# barrieren-a-2.net
KiCad netlist of a schematic drawn in EAGLE
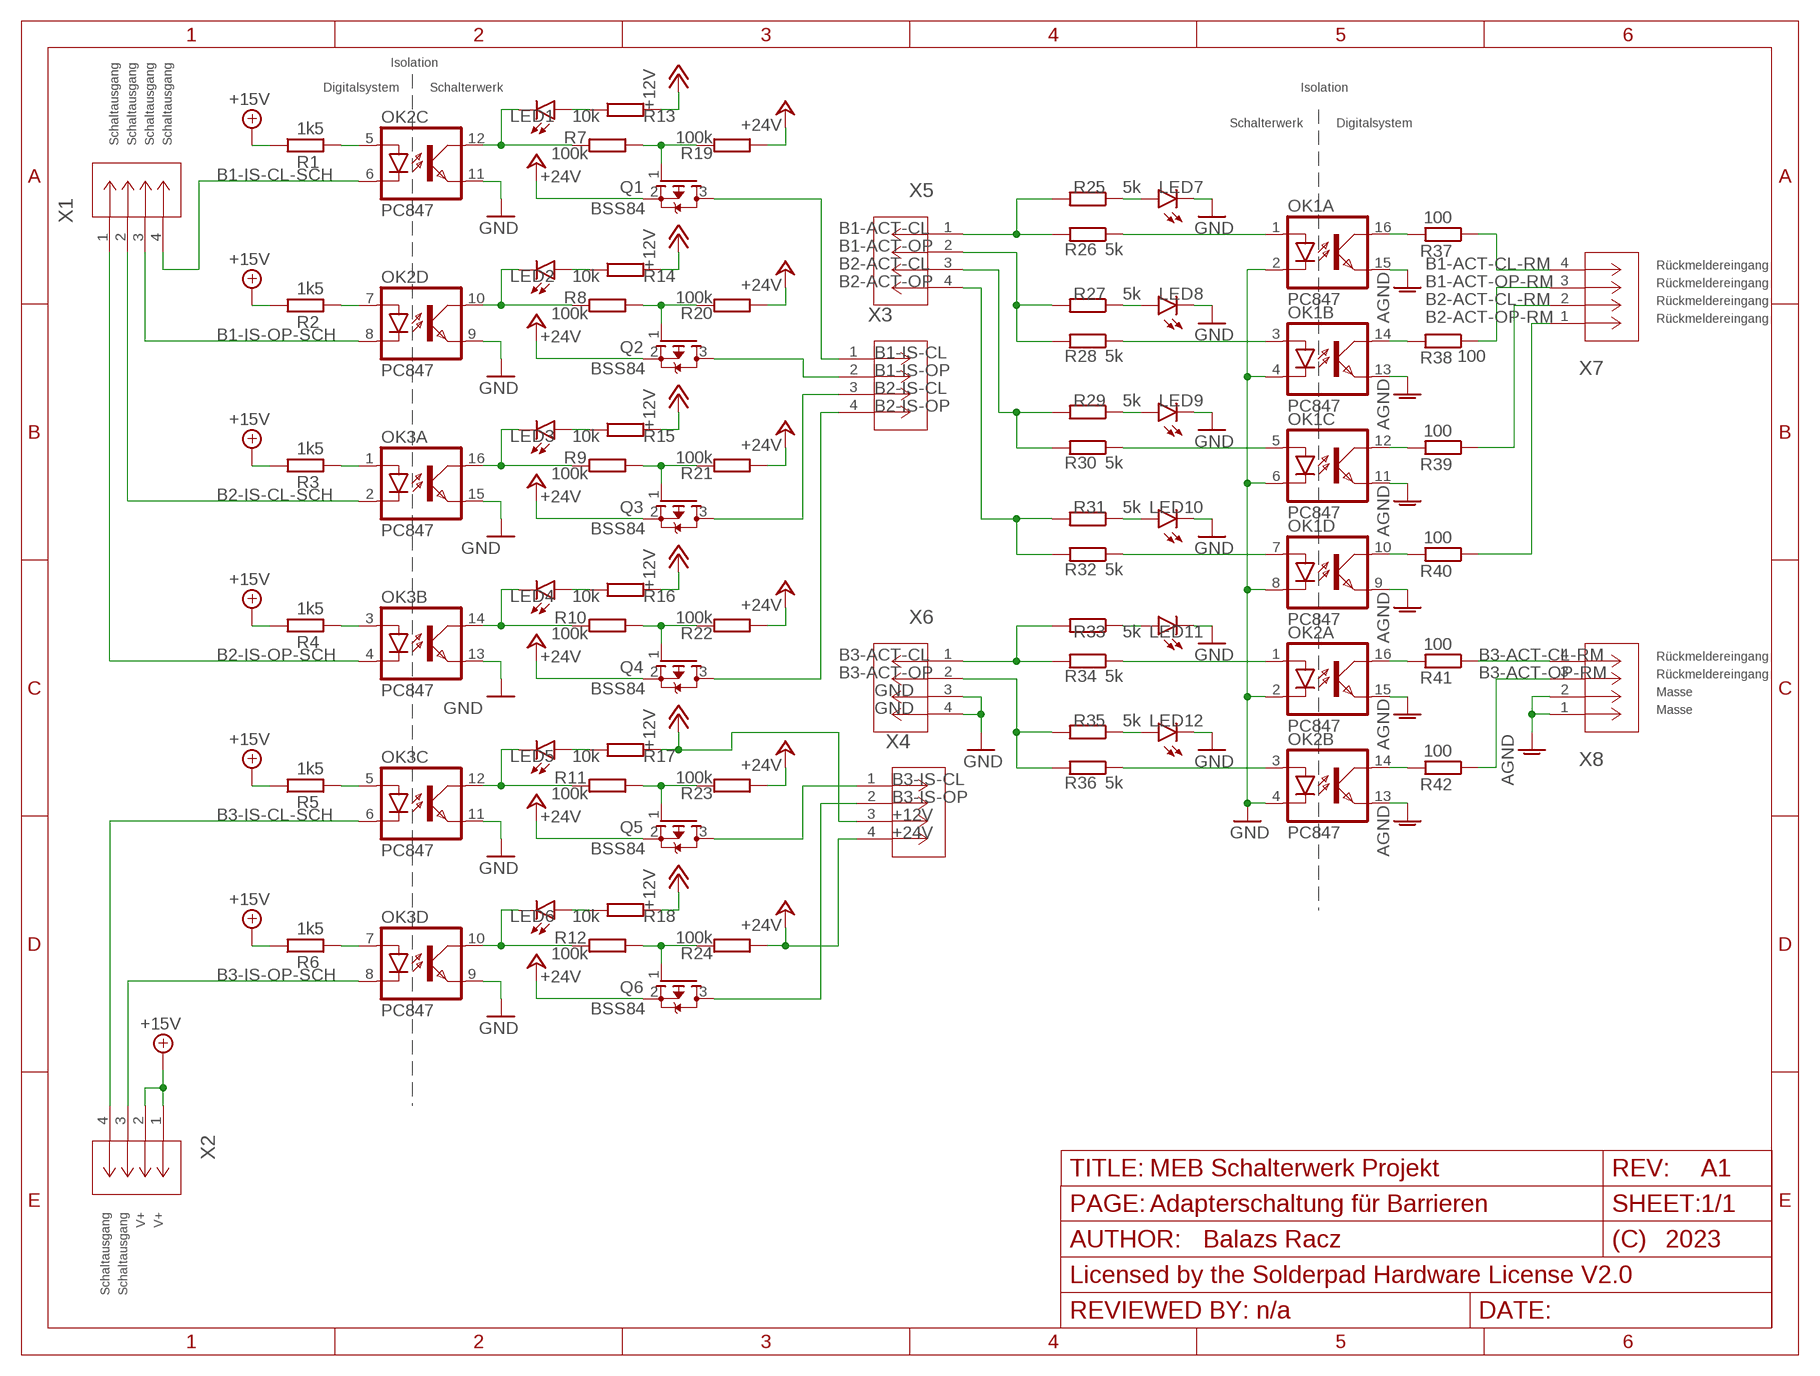
[diagram p0: schematic, sheet 1]

(export (version "E")
  (design (tool "Eeschema 10.0.6"))
  (components
    (comp (ref "LED1")
      (value "LEDCHIPLED_0603")
      (footprint "eagle-import:CHIPLED_0603")
      (libsource (lib "eagle-import") (part "LEDCHIPLED_0603"))
    )
    (comp (ref "LED2")
      (value "LEDCHIPLED_0603")
      (footprint "eagle-import:CHIPLED_0603")
      (libsource (lib "eagle-import") (part "LEDCHIPLED_0603"))
    )
    (comp (ref "LED3")
      (value "LEDCHIPLED_0603")
      (footprint "eagle-import:CHIPLED_0603")
      (libsource (lib "eagle-import") (part "LEDCHIPLED_0603"))
    )
    (comp (ref "LED4")
      (value "LEDCHIPLED_0603")
      (footprint "eagle-import:CHIPLED_0603")
      (libsource (lib "eagle-import") (part "LEDCHIPLED_0603"))
    )
    (comp (ref "LED5")
      (value "LEDCHIPLED_0603")
      (footprint "eagle-import:CHIPLED_0603")
      (libsource (lib "eagle-import") (part "LEDCHIPLED_0603"))
    )
    (comp (ref "LED6")
      (value "LEDCHIPLED_0603")
      (footprint "eagle-import:CHIPLED_0603")
      (libsource (lib "eagle-import") (part "LEDCHIPLED_0603"))
    )
    (comp (ref "LED7")
      (value "LEDCHIPLED_0603")
      (footprint "eagle-import:CHIPLED_0603")
      (libsource (lib "eagle-import") (part "LEDCHIPLED_0603"))
    )
    (comp (ref "LED8")
      (value "LEDCHIPLED_0603")
      (footprint "eagle-import:CHIPLED_0603")
      (libsource (lib "eagle-import") (part "LEDCHIPLED_0603"))
    )
    (comp (ref "LED9")
      (value "LEDCHIPLED_0603")
      (footprint "eagle-import:CHIPLED_0603")
      (libsource (lib "eagle-import") (part "LEDCHIPLED_0603"))
    )
    (comp (ref "LED10")
      (value "LEDCHIPLED_0603")
      (footprint "eagle-import:CHIPLED_0603")
      (libsource (lib "eagle-import") (part "LEDCHIPLED_0603"))
    )
    (comp (ref "LED11")
      (value "LEDCHIPLED_0603")
      (footprint "eagle-import:CHIPLED_0603")
      (libsource (lib "eagle-import") (part "LEDCHIPLED_0603"))
    )
    (comp (ref "LED12")
      (value "LEDCHIPLED_0603")
      (footprint "eagle-import:CHIPLED_0603")
      (libsource (lib "eagle-import") (part "LEDCHIPLED_0603"))
    )
    (comp (ref "OK1")
      (value "PC847")
      (footprint "eagle-import:DIL16")
      (libsource (lib "eagle-import") (part "PC847"))
    )
    (comp (ref "OK2")
      (value "PC847")
      (footprint "eagle-import:DIL16")
      (libsource (lib "eagle-import") (part "PC847"))
    )
    (comp (ref "OK3")
      (value "PC847")
      (footprint "eagle-import:DIL16")
      (libsource (lib "eagle-import") (part "PC847"))
    )
    (comp (ref "Q1")
      (value "BSS84")
      (footprint "eagle-import:SOT23-PCH")
      (libsource (lib "eagle-import") (part "BSS84"))
    )
    (comp (ref "Q2")
      (value "BSS84")
      (footprint "eagle-import:SOT23-PCH")
      (libsource (lib "eagle-import") (part "BSS84"))
    )
    (comp (ref "Q3")
      (value "BSS84")
      (footprint "eagle-import:SOT23-PCH")
      (libsource (lib "eagle-import") (part "BSS84"))
    )
    (comp (ref "Q4")
      (value "BSS84")
      (footprint "eagle-import:SOT23-PCH")
      (libsource (lib "eagle-import") (part "BSS84"))
    )
    (comp (ref "Q5")
      (value "BSS84")
      (footprint "eagle-import:SOT23-PCH")
      (libsource (lib "eagle-import") (part "BSS84"))
    )
    (comp (ref "Q6")
      (value "BSS84")
      (footprint "eagle-import:SOT23-PCH")
      (libsource (lib "eagle-import") (part "BSS84"))
    )
    (comp (ref "R1")
      (value "1k5")
      (footprint "eagle-import:R0805")
      (libsource (lib "eagle-import") (part "R-EU_R0805"))
    )
    (comp (ref "R2")
      (value "1k5")
      (footprint "eagle-import:R0805")
      (libsource (lib "eagle-import") (part "R-EU_R0805"))
    )
    (comp (ref "R3")
      (value "1k5")
      (footprint "eagle-import:R0805")
      (libsource (lib "eagle-import") (part "R-EU_R0805"))
    )
    (comp (ref "R4")
      (value "1k5")
      (footprint "eagle-import:R0805")
      (libsource (lib "eagle-import") (part "R-EU_R0805"))
    )
    (comp (ref "R5")
      (value "1k5")
      (footprint "eagle-import:R0805")
      (libsource (lib "eagle-import") (part "R-EU_R0805"))
    )
    (comp (ref "R6")
      (value "1k5")
      (footprint "eagle-import:R0805")
      (libsource (lib "eagle-import") (part "R-EU_R0805"))
    )
    (comp (ref "R7")
      (value "100k")
      (footprint "eagle-import:R0805")
      (libsource (lib "eagle-import") (part "R-EU_R0805"))
    )
    (comp (ref "R8")
      (value "100k")
      (footprint "eagle-import:R0805")
      (libsource (lib "eagle-import") (part "R-EU_R0805"))
    )
    (comp (ref "R9")
      (value "100k")
      (footprint "eagle-import:R0805")
      (libsource (lib "eagle-import") (part "R-EU_R0805"))
    )
    (comp (ref "R10")
      (value "100k")
      (footprint "eagle-import:R0805")
      (libsource (lib "eagle-import") (part "R-EU_R0805"))
    )
    (comp (ref "R11")
      (value "100k")
      (footprint "eagle-import:R0805")
      (libsource (lib "eagle-import") (part "R-EU_R0805"))
    )
    (comp (ref "R12")
      (value "100k")
      (footprint "eagle-import:R0805")
      (libsource (lib "eagle-import") (part "R-EU_R0805"))
    )
    (comp (ref "R13")
      (value "10k")
      (footprint "eagle-import:R0805")
      (libsource (lib "eagle-import") (part "R-EU_R0805"))
    )
    (comp (ref "R14")
      (value "10k")
      (footprint "eagle-import:R0805")
      (libsource (lib "eagle-import") (part "R-EU_R0805"))
    )
    (comp (ref "R15")
      (value "10k")
      (footprint "eagle-import:R0805")
      (libsource (lib "eagle-import") (part "R-EU_R0805"))
    )
    (comp (ref "R16")
      (value "10k")
      (footprint "eagle-import:R0805")
      (libsource (lib "eagle-import") (part "R-EU_R0805"))
    )
    (comp (ref "R17")
      (value "10k")
      (footprint "eagle-import:R0805")
      (libsource (lib "eagle-import") (part "R-EU_R0805"))
    )
    (comp (ref "R18")
      (value "10k")
      (footprint "eagle-import:R0805")
      (libsource (lib "eagle-import") (part "R-EU_R0805"))
    )
    (comp (ref "R19")
      (value "100k")
      (footprint "eagle-import:R0805")
      (libsource (lib "eagle-import") (part "R-EU_R0805"))
    )
    (comp (ref "R20")
      (value "100k")
      (footprint "eagle-import:R0805")
      (libsource (lib "eagle-import") (part "R-EU_R0805"))
    )
    (comp (ref "R21")
      (value "100k")
      (footprint "eagle-import:R0805")
      (libsource (lib "eagle-import") (part "R-EU_R0805"))
    )
    (comp (ref "R22")
      (value "100k")
      (footprint "eagle-import:R0805")
      (libsource (lib "eagle-import") (part "R-EU_R0805"))
    )
    (comp (ref "R23")
      (value "100k")
      (footprint "eagle-import:R0805")
      (libsource (lib "eagle-import") (part "R-EU_R0805"))
    )
    (comp (ref "R24")
      (value "100k")
      (footprint "eagle-import:R0805")
      (libsource (lib "eagle-import") (part "R-EU_R0805"))
    )
    (comp (ref "R25")
      (value "5k")
      (footprint "eagle-import:R0805")
      (libsource (lib "eagle-import") (part "R-EU_R0805"))
    )
    (comp (ref "R26")
      (value "5k")
      (footprint "eagle-import:R0805")
      (libsource (lib "eagle-import") (part "R-EU_R0805"))
    )
    (comp (ref "R27")
      (value "5k")
      (footprint "eagle-import:R0805")
      (libsource (lib "eagle-import") (part "R-EU_R0805"))
    )
    (comp (ref "R28")
      (value "5k")
      (footprint "eagle-import:R0805")
      (libsource (lib "eagle-import") (part "R-EU_R0805"))
    )
    (comp (ref "R29")
      (value "5k")
      (footprint "eagle-import:R0805")
      (libsource (lib "eagle-import") (part "R-EU_R0805"))
    )
    (comp (ref "R30")
      (value "5k")
      (footprint "eagle-import:R0805")
      (libsource (lib "eagle-import") (part "R-EU_R0805"))
    )
    (comp (ref "R31")
      (value "5k")
      (footprint "eagle-import:R0805")
      (libsource (lib "eagle-import") (part "R-EU_R0805"))
    )
    (comp (ref "R32")
      (value "5k")
      (footprint "eagle-import:R0805")
      (libsource (lib "eagle-import") (part "R-EU_R0805"))
    )
    (comp (ref "R33")
      (value "5k")
      (footprint "eagle-import:R0805")
      (libsource (lib "eagle-import") (part "R-EU_R0805"))
    )
    (comp (ref "R34")
      (value "5k")
      (footprint "eagle-import:R0805")
      (libsource (lib "eagle-import") (part "R-EU_R0805"))
    )
    (comp (ref "R35")
      (value "5k")
      (footprint "eagle-import:R0805")
      (libsource (lib "eagle-import") (part "R-EU_R0805"))
    )
    (comp (ref "R36")
      (value "5k")
      (footprint "eagle-import:R0805")
      (libsource (lib "eagle-import") (part "R-EU_R0805"))
    )
    (comp (ref "R37")
      (value "100")
      (footprint "eagle-import:R0805")
      (libsource (lib "eagle-import") (part "R-EU_R0805"))
    )
    (comp (ref "R38")
      (value "100")
      (footprint "eagle-import:R0805")
      (libsource (lib "eagle-import") (part "R-EU_R0805"))
    )
    (comp (ref "R39")
      (value "100")
      (footprint "eagle-import:R0805")
      (libsource (lib "eagle-import") (part "R-EU_R0805"))
    )
    (comp (ref "R40")
      (value "100")
      (footprint "eagle-import:R0805")
      (libsource (lib "eagle-import") (part "R-EU_R0805"))
    )
    (comp (ref "R41")
      (value "100")
      (footprint "eagle-import:R0805")
      (libsource (lib "eagle-import") (part "R-EU_R0805"))
    )
    (comp (ref "R42")
      (value "100")
      (footprint "eagle-import:R0805")
      (libsource (lib "eagle-import") (part "R-EU_R0805"))
    )
    (comp (ref "X1")
      (value "PHNX_4P_350CONN_1984989_PXC")
      (footprint "eagle-import:PHNX_4P_350")
      (fields
        (field (name "MANUFACTURER_PART_NUMBER") "1984989")
        (field (name "COPYRIGHT") "Copyright (C) 2023 Ultra Librarian. All rights reserved.")
      )
      (libsource (lib "eagle-import") (part "PHNX_4P_350CONN_1984989_PXC"))
    )
    (comp (ref "X2")
      (value "PHNX_4P_350CONN_1984989_PXC")
      (footprint "eagle-import:PHNX_4P_350")
      (fields
        (field (name "MANUFACTURER_PART_NUMBER") "1984989")
        (field (name "COPYRIGHT") "Copyright (C) 2023 Ultra Librarian. All rights reserved.")
      )
      (libsource (lib "eagle-import") (part "PHNX_4P_350CONN_1984989_PXC"))
    )
    (comp (ref "X3")
      (value "PHNX_4P_350CONN_1984989_PXC")
      (footprint "eagle-import:PHNX_4P_350")
      (fields
        (field (name "MANUFACTURER_PART_NUMBER") "1984989")
        (field (name "COPYRIGHT") "Copyright (C) 2023 Ultra Librarian. All rights reserved.")
      )
      (libsource (lib "eagle-import") (part "PHNX_4P_350CONN_1984989_PXC"))
    )
    (comp (ref "X4")
      (value "PHNX_4P_350CONN_1984989_PXC")
      (footprint "eagle-import:PHNX_4P_350")
      (fields
        (field (name "MANUFACTURER_PART_NUMBER") "1984989")
        (field (name "COPYRIGHT") "Copyright (C) 2023 Ultra Librarian. All rights reserved.")
      )
      (libsource (lib "eagle-import") (part "PHNX_4P_350CONN_1984989_PXC"))
    )
    (comp (ref "X5")
      (value "PHNX_4P_350CONN_1984989_PXC")
      (footprint "eagle-import:PHNX_4P_350")
      (fields
        (field (name "MANUFACTURER_PART_NUMBER") "1984989")
        (field (name "COPYRIGHT") "Copyright (C) 2023 Ultra Librarian. All rights reserved.")
      )
      (libsource (lib "eagle-import") (part "PHNX_4P_350CONN_1984989_PXC"))
    )
    (comp (ref "X6")
      (value "PHNX_4P_350CONN_1984989_PXC")
      (footprint "eagle-import:PHNX_4P_350")
      (fields
        (field (name "MANUFACTURER_PART_NUMBER") "1984989")
        (field (name "COPYRIGHT") "Copyright (C) 2023 Ultra Librarian. All rights reserved.")
      )
      (libsource (lib "eagle-import") (part "PHNX_4P_350CONN_1984989_PXC"))
    )
    (comp (ref "X7")
      (value "PHNX_4P_350CONN_1984989_PXC")
      (footprint "eagle-import:PHNX_4P_350")
      (fields
        (field (name "MANUFACTURER_PART_NUMBER") "1984989")
        (field (name "COPYRIGHT") "Copyright (C) 2023 Ultra Librarian. All rights reserved.")
      )
      (libsource (lib "eagle-import") (part "PHNX_4P_350CONN_1984989_PXC"))
    )
    (comp (ref "X8")
      (value "PHNX_4P_350CONN_1984989_PXC")
      (footprint "eagle-import:PHNX_4P_350")
      (fields
        (field (name "MANUFACTURER_PART_NUMBER") "1984989")
        (field (name "COPYRIGHT") "Copyright (C) 2023 Ultra Librarian. All rights reserved.")
      )
      (libsource (lib "eagle-import") (part "PHNX_4P_350CONN_1984989_PXC"))
    )
  )
  (nets
    (net (code "1") (name "+12V") (class "Default")
      (node (ref "R13") (pin "2") (pinfunction "2_2") (pintype "passive"))
      (node (ref "R14") (pin "2") (pinfunction "2_2") (pintype "passive"))
      (node (ref "R15") (pin "2") (pinfunction "2_2") (pintype "passive"))
      (node (ref "R16") (pin "2") (pinfunction "2_2") (pintype "passive"))
      (node (ref "R17") (pin "2") (pinfunction "2_2") (pintype "passive"))
      (node (ref "R18") (pin "2") (pinfunction "2_2") (pintype "passive"))
      (node (ref "X4") (pin "3") (pinfunction "3_3") (pintype "passive"))
    )
    (net (code "2") (name "+15V") (class "Default")
      (node (ref "R1") (pin "1") (pinfunction "1_1") (pintype "passive"))
      (node (ref "R2") (pin "1") (pinfunction "1_1") (pintype "passive"))
      (node (ref "R3") (pin "1") (pinfunction "1_1") (pintype "passive"))
      (node (ref "R4") (pin "1") (pinfunction "1_1") (pintype "passive"))
      (node (ref "R5") (pin "1") (pinfunction "1_1") (pintype "passive"))
      (node (ref "R6") (pin "1") (pinfunction "1_1") (pintype "passive"))
      (node (ref "X2") (pin "1") (pinfunction "1_1") (pintype "passive"))
      (node (ref "X2") (pin "2") (pinfunction "2_2") (pintype "passive"))
    )
    (net (code "3") (name "+24V") (class "Default")
      (node (ref "Q1") (pin "2") (pinfunction "S_2") (pintype "passive"))
      (node (ref "Q2") (pin "2") (pinfunction "S_2") (pintype "passive"))
      (node (ref "Q3") (pin "2") (pinfunction "S_2") (pintype "passive"))
      (node (ref "Q4") (pin "2") (pinfunction "S_2") (pintype "passive"))
      (node (ref "Q5") (pin "2") (pinfunction "S_2") (pintype "passive"))
      (node (ref "Q6") (pin "2") (pinfunction "S_2") (pintype "passive"))
      (node (ref "R19") (pin "2") (pinfunction "2_2") (pintype "passive"))
      (node (ref "R20") (pin "2") (pinfunction "2_2") (pintype "passive"))
      (node (ref "R21") (pin "2") (pinfunction "2_2") (pintype "passive"))
      (node (ref "R22") (pin "2") (pinfunction "2_2") (pintype "passive"))
      (node (ref "R23") (pin "2") (pinfunction "2_2") (pintype "passive"))
      (node (ref "R24") (pin "2") (pinfunction "2_2") (pintype "passive"))
      (node (ref "X4") (pin "4") (pinfunction "4_4") (pintype "passive"))
    )
    (net (code "4") (name "/B1-ACT-CL") (class "Default")
      (node (ref "R25") (pin "2") (pinfunction "2_2") (pintype "passive"))
      (node (ref "R26") (pin "2") (pinfunction "2_2") (pintype "passive"))
      (node (ref "X5") (pin "1") (pinfunction "1_1") (pintype "passive"))
    )
    (net (code "5") (name "/B1-ACT-CL-RM") (class "Default")
      (node (ref "R37") (pin "1") (pinfunction "1_1") (pintype "passive"))
      (node (ref "X7") (pin "4") (pinfunction "4_4") (pintype "passive"))
    )
    (net (code "6") (name "/B1-ACT-OP") (class "Default")
      (node (ref "R27") (pin "2") (pinfunction "2_2") (pintype "passive"))
      (node (ref "R28") (pin "2") (pinfunction "2_2") (pintype "passive"))
      (node (ref "X5") (pin "2") (pinfunction "2_2") (pintype "passive"))
    )
    (net (code "7") (name "/B1-ACT-OP-RM") (class "Default")
      (node (ref "R38") (pin "1") (pinfunction "1_1") (pintype "passive"))
      (node (ref "X7") (pin "3") (pinfunction "3_3") (pintype "passive"))
    )
    (net (code "8") (name "/B1-IS-CL") (class "Default")
      (node (ref "Q1") (pin "3") (pinfunction "D_3") (pintype "passive"))
      (node (ref "X3") (pin "1") (pinfunction "1_1") (pintype "passive"))
    )
    (net (code "9") (name "/B1-IS-CL-SCH") (class "Default")
      (node (ref "OK2") (pin "6") (pinfunction "C_6") (pintype "passive"))
      (node (ref "X1") (pin "4") (pinfunction "4_4") (pintype "passive"))
    )
    (net (code "10") (name "/B1-IS-OP") (class "Default")
      (node (ref "Q2") (pin "3") (pinfunction "D_3") (pintype "passive"))
      (node (ref "X3") (pin "2") (pinfunction "2_2") (pintype "passive"))
    )
    (net (code "11") (name "/B1-IS-OP-SCH") (class "Default")
      (node (ref "OK2") (pin "8") (pinfunction "C_8") (pintype "passive"))
      (node (ref "X1") (pin "3") (pinfunction "3_3") (pintype "passive"))
    )
    (net (code "12") (name "/B2-ACT-CL") (class "Default")
      (node (ref "R29") (pin "2") (pinfunction "2_2") (pintype "passive"))
      (node (ref "R30") (pin "2") (pinfunction "2_2") (pintype "passive"))
      (node (ref "X5") (pin "3") (pinfunction "3_3") (pintype "passive"))
    )
    (net (code "13") (name "/B2-ACT-CL-RM") (class "Default")
      (node (ref "R39") (pin "1") (pinfunction "1_1") (pintype "passive"))
      (node (ref "X7") (pin "2") (pinfunction "2_2") (pintype "passive"))
    )
    (net (code "14") (name "/B2-ACT-OP") (class "Default")
      (node (ref "R31") (pin "2") (pinfunction "2_2") (pintype "passive"))
      (node (ref "R32") (pin "2") (pinfunction "2_2") (pintype "passive"))
      (node (ref "X5") (pin "4") (pinfunction "4_4") (pintype "passive"))
    )
    (net (code "15") (name "/B2-ACT-OP-RM") (class "Default")
      (node (ref "R40") (pin "1") (pinfunction "1_1") (pintype "passive"))
      (node (ref "X7") (pin "1") (pinfunction "1_1") (pintype "passive"))
    )
    (net (code "16") (name "/B2-IS-CL") (class "Default")
      (node (ref "Q3") (pin "3") (pinfunction "D_3") (pintype "passive"))
      (node (ref "X3") (pin "3") (pinfunction "3_3") (pintype "passive"))
    )
    (net (code "17") (name "/B2-IS-CL-SCH") (class "Default")
      (node (ref "OK3") (pin "2") (pinfunction "C_2") (pintype "passive"))
      (node (ref "X1") (pin "2") (pinfunction "2_2") (pintype "passive"))
    )
    (net (code "18") (name "/B2-IS-OP") (class "Default")
      (node (ref "Q4") (pin "3") (pinfunction "D_3") (pintype "passive"))
      (node (ref "X3") (pin "4") (pinfunction "4_4") (pintype "passive"))
    )
    (net (code "19") (name "/B2-IS-OP-SCH") (class "Default")
      (node (ref "OK3") (pin "4") (pinfunction "C_4") (pintype "passive"))
      (node (ref "X1") (pin "1") (pinfunction "1_1") (pintype "passive"))
    )
    (net (code "20") (name "/B3-ACT-CL") (class "Default")
      (node (ref "R33") (pin "2") (pinfunction "2_2") (pintype "passive"))
      (node (ref "R34") (pin "2") (pinfunction "2_2") (pintype "passive"))
      (node (ref "X6") (pin "1") (pinfunction "1_1") (pintype "passive"))
    )
    (net (code "21") (name "/B3-ACT-CL-RM") (class "Default")
      (node (ref "R41") (pin "1") (pinfunction "1_1") (pintype "passive"))
      (node (ref "X8") (pin "4") (pinfunction "4_4") (pintype "passive"))
    )
    (net (code "22") (name "/B3-ACT-OP") (class "Default")
      (node (ref "R35") (pin "2") (pinfunction "2_2") (pintype "passive"))
      (node (ref "R36") (pin "2") (pinfunction "2_2") (pintype "passive"))
      (node (ref "X6") (pin "2") (pinfunction "2_2") (pintype "passive"))
    )
    (net (code "23") (name "/B3-ACT-OP-RM") (class "Default")
      (node (ref "R42") (pin "1") (pinfunction "1_1") (pintype "passive"))
      (node (ref "X8") (pin "3") (pinfunction "3_3") (pintype "passive"))
    )
    (net (code "24") (name "/B3-IS-CL") (class "Default")
      (node (ref "Q5") (pin "3") (pinfunction "D_3") (pintype "passive"))
      (node (ref "X4") (pin "1") (pinfunction "1_1") (pintype "passive"))
    )
    (net (code "25") (name "/B3-IS-CL-SCH") (class "Default")
      (node (ref "OK3") (pin "6") (pinfunction "C_6") (pintype "passive"))
      (node (ref "X2") (pin "4") (pinfunction "4_4") (pintype "passive"))
    )
    (net (code "26") (name "/B3-IS-OP") (class "Default")
      (node (ref "Q6") (pin "3") (pinfunction "D_3") (pintype "passive"))
      (node (ref "X4") (pin "2") (pinfunction "2_2") (pintype "passive"))
    )
    (net (code "27") (name "/B3-IS-OP-SCH") (class "Default")
      (node (ref "OK3") (pin "8") (pinfunction "C_8") (pintype "passive"))
      (node (ref "X2") (pin "3") (pinfunction "3_3") (pintype "passive"))
    )
    (net (code "28") (name "AGND") (class "Default")
      (node (ref "OK1") (pin "11") (pinfunction "EMIT_11") (pintype "passive"))
      (node (ref "OK1") (pin "13") (pinfunction "EMIT_13") (pintype "passive"))
      (node (ref "OK1") (pin "15") (pinfunction "EMIT_15") (pintype "passive"))
      (node (ref "OK1") (pin "9") (pinfunction "EMIT_9") (pintype "passive"))
      (node (ref "OK2") (pin "13") (pinfunction "EMIT_13") (pintype "passive"))
      (node (ref "OK2") (pin "15") (pinfunction "EMIT_15") (pintype "passive"))
      (node (ref "X8") (pin "1") (pinfunction "1_1") (pintype "passive"))
      (node (ref "X8") (pin "2") (pinfunction "2_2") (pintype "passive"))
    )
    (net (code "29") (name "GND") (class "Default")
      (node (ref "LED10") (pin "C") (pinfunction "C_C") (pintype "passive"))
      (node (ref "LED11") (pin "C") (pinfunction "C_C") (pintype "passive"))
      (node (ref "LED12") (pin "C") (pinfunction "C_C") (pintype "passive"))
      (node (ref "LED7") (pin "C") (pinfunction "C_C") (pintype "passive"))
      (node (ref "LED8") (pin "C") (pinfunction "C_C") (pintype "passive"))
      (node (ref "LED9") (pin "C") (pinfunction "C_C") (pintype "passive"))
      (node (ref "OK1") (pin "2") (pinfunction "C_2") (pintype "passive"))
      (node (ref "OK1") (pin "4") (pinfunction "C_4") (pintype "passive"))
      (node (ref "OK1") (pin "6") (pinfunction "C_6") (pintype "passive"))
      (node (ref "OK1") (pin "8") (pinfunction "C_8") (pintype "passive"))
      (node (ref "OK2") (pin "11") (pinfunction "EMIT_11") (pintype "passive"))
      (node (ref "OK2") (pin "2") (pinfunction "C_2") (pintype "passive"))
      (node (ref "OK2") (pin "4") (pinfunction "C_4") (pintype "passive"))
      (node (ref "OK2") (pin "9") (pinfunction "EMIT_9") (pintype "passive"))
      (node (ref "OK3") (pin "11") (pinfunction "EMIT_11") (pintype "passive"))
      (node (ref "OK3") (pin "13") (pinfunction "EMIT_13") (pintype "passive"))
      (node (ref "OK3") (pin "15") (pinfunction "EMIT_15") (pintype "passive"))
      (node (ref "OK3") (pin "9") (pinfunction "EMIT_9") (pintype "passive"))
      (node (ref "X6") (pin "3") (pinfunction "3_3") (pintype "passive"))
      (node (ref "X6") (pin "4") (pinfunction "4_4") (pintype "passive"))
    )
    (net (code "30") (name "Net-(LED1-PadA)") (class "Default")
      (node (ref "LED1") (pin "A") (pinfunction "A_A") (pintype "passive"))
      (node (ref "R13") (pin "1") (pinfunction "1_1") (pintype "passive"))
    )
    (net (code "31") (name "Net-(LED2-PadA)") (class "Default")
      (node (ref "LED2") (pin "A") (pinfunction "A_A") (pintype "passive"))
      (node (ref "R14") (pin "1") (pinfunction "1_1") (pintype "passive"))
    )
    (net (code "32") (name "Net-(LED3-PadA)") (class "Default")
      (node (ref "LED3") (pin "A") (pinfunction "A_A") (pintype "passive"))
      (node (ref "R15") (pin "1") (pinfunction "1_1") (pintype "passive"))
    )
    (net (code "33") (name "Net-(LED4-PadA)") (class "Default")
      (node (ref "LED4") (pin "A") (pinfunction "A_A") (pintype "passive"))
      (node (ref "R16") (pin "1") (pinfunction "1_1") (pintype "passive"))
    )
    (net (code "34") (name "Net-(LED5-PadA)") (class "Default")
      (node (ref "LED5") (pin "A") (pinfunction "A_A") (pintype "passive"))
      (node (ref "R17") (pin "1") (pinfunction "1_1") (pintype "passive"))
    )
    (net (code "35") (name "Net-(LED6-PadA)") (class "Default")
      (node (ref "LED6") (pin "A") (pinfunction "A_A") (pintype "passive"))
      (node (ref "R18") (pin "1") (pinfunction "1_1") (pintype "passive"))
    )
    (net (code "36") (name "Net-(LED7-PadA)") (class "Default")
      (node (ref "LED7") (pin "A") (pinfunction "A_A") (pintype "passive"))
      (node (ref "R25") (pin "1") (pinfunction "1_1") (pintype "passive"))
    )
    (net (code "37") (name "Net-(LED8-PadA)") (class "Default")
      (node (ref "LED8") (pin "A") (pinfunction "A_A") (pintype "passive"))
      (node (ref "R27") (pin "1") (pinfunction "1_1") (pintype "passive"))
    )
    (net (code "38") (name "Net-(LED9-PadA)") (class "Default")
      (node (ref "LED9") (pin "A") (pinfunction "A_A") (pintype "passive"))
      (node (ref "R29") (pin "1") (pinfunction "1_1") (pintype "passive"))
    )
    (net (code "39") (name "Net-(LED10-PadA)") (class "Default")
      (node (ref "LED10") (pin "A") (pinfunction "A_A") (pintype "passive"))
      (node (ref "R31") (pin "1") (pinfunction "1_1") (pintype "passive"))
    )
    (net (code "40") (name "Net-(LED11-PadA)") (class "Default")
      (node (ref "LED11") (pin "A") (pinfunction "A_A") (pintype "passive"))
      (node (ref "R33") (pin "1") (pinfunction "1_1") (pintype "passive"))
    )
    (net (code "41") (name "Net-(LED12-PadA)") (class "Default")
      (node (ref "LED12") (pin "A") (pinfunction "A_A") (pintype "passive"))
      (node (ref "R35") (pin "1") (pinfunction "1_1") (pintype "passive"))
    )
    (net (code "42") (name "Net-(OK1A-A)") (class "Default")
      (node (ref "OK1") (pin "1") (pinfunction "A_1") (pintype "passive"))
      (node (ref "R26") (pin "1") (pinfunction "1_1") (pintype "passive"))
    )
    (net (code "43") (name "Net-(OK1A-COL)") (class "Default")
      (node (ref "OK1") (pin "16") (pinfunction "COL_16") (pintype "passive"))
      (node (ref "R37") (pin "2") (pinfunction "2_2") (pintype "passive"))
    )
    (net (code "44") (name "Net-(OK1B-A)") (class "Default")
      (node (ref "OK1") (pin "3") (pinfunction "A_3") (pintype "passive"))
      (node (ref "R28") (pin "1") (pinfunction "1_1") (pintype "passive"))
    )
    (net (code "45") (name "Net-(OK1B-COL)") (class "Default")
      (node (ref "OK1") (pin "14") (pinfunction "COL_14") (pintype "passive"))
      (node (ref "R38") (pin "2") (pinfunction "2_2") (pintype "passive"))
    )
    (net (code "46") (name "Net-(OK1C-A)") (class "Default")
      (node (ref "OK1") (pin "5") (pinfunction "A_5") (pintype "passive"))
      (node (ref "R30") (pin "1") (pinfunction "1_1") (pintype "passive"))
    )
    (net (code "47") (name "Net-(OK1C-COL)") (class "Default")
      (node (ref "OK1") (pin "12") (pinfunction "COL_12") (pintype "passive"))
      (node (ref "R39") (pin "2") (pinfunction "2_2") (pintype "passive"))
    )
    (net (code "48") (name "Net-(OK1D-A)") (class "Default")
      (node (ref "OK1") (pin "7") (pinfunction "A_7") (pintype "passive"))
      (node (ref "R32") (pin "1") (pinfunction "1_1") (pintype "passive"))
    )
    (net (code "49") (name "Net-(OK1D-COL)") (class "Default")
      (node (ref "OK1") (pin "10") (pinfunction "COL_10") (pintype "passive"))
      (node (ref "R40") (pin "2") (pinfunction "2_2") (pintype "passive"))
    )
    (net (code "50") (name "Net-(OK2A-A)") (class "Default")
      (node (ref "OK2") (pin "1") (pinfunction "A_1") (pintype "passive"))
      (node (ref "R34") (pin "1") (pinfunction "1_1") (pintype "passive"))
    )
    (net (code "51") (name "Net-(OK2A-COL)") (class "Default")
      (node (ref "OK2") (pin "16") (pinfunction "COL_16") (pintype "passive"))
      (node (ref "R41") (pin "2") (pinfunction "2_2") (pintype "passive"))
    )
    (net (code "52") (name "Net-(OK2B-A)") (class "Default")
      (node (ref "OK2") (pin "3") (pinfunction "A_3") (pintype "passive"))
      (node (ref "R36") (pin "1") (pinfunction "1_1") (pintype "passive"))
    )
    (net (code "53") (name "Net-(OK2B-COL)") (class "Default")
      (node (ref "OK2") (pin "14") (pinfunction "COL_14") (pintype "passive"))
      (node (ref "R42") (pin "2") (pinfunction "2_2") (pintype "passive"))
    )
    (net (code "54") (name "Net-(OK2C-A)") (class "Default")
      (node (ref "OK2") (pin "5") (pinfunction "A_5") (pintype "passive"))
      (node (ref "R1") (pin "2") (pinfunction "2_2") (pintype "passive"))
    )
    (net (code "55") (name "Net-(OK2C-COL)") (class "Default")
      (node (ref "LED1") (pin "C") (pinfunction "C_C") (pintype "passive"))
      (node (ref "OK2") (pin "12") (pinfunction "COL_12") (pintype "passive"))
      (node (ref "R7") (pin "2") (pinfunction "2_2") (pintype "passive"))
    )
    (net (code "56") (name "Net-(OK2D-A)") (class "Default")
      (node (ref "OK2") (pin "7") (pinfunction "A_7") (pintype "passive"))
      (node (ref "R2") (pin "2") (pinfunction "2_2") (pintype "passive"))
    )
    (net (code "57") (name "Net-(OK2D-COL)") (class "Default")
      (node (ref "LED2") (pin "C") (pinfunction "C_C") (pintype "passive"))
      (node (ref "OK2") (pin "10") (pinfunction "COL_10") (pintype "passive"))
      (node (ref "R8") (pin "2") (pinfunction "2_2") (pintype "passive"))
    )
    (net (code "58") (name "Net-(OK3A-A)") (class "Default")
      (node (ref "OK3") (pin "1") (pinfunction "A_1") (pintype "passive"))
      (node (ref "R3") (pin "2") (pinfunction "2_2") (pintype "passive"))
    )
    (net (code "59") (name "Net-(OK3A-COL)") (class "Default")
      (node (ref "LED3") (pin "C") (pinfunction "C_C") (pintype "passive"))
      (node (ref "OK3") (pin "16") (pinfunction "COL_16") (pintype "passive"))
      (node (ref "R9") (pin "2") (pinfunction "2_2") (pintype "passive"))
    )
    (net (code "60") (name "Net-(OK3B-A)") (class "Default")
      (node (ref "OK3") (pin "3") (pinfunction "A_3") (pintype "passive"))
      (node (ref "R4") (pin "2") (pinfunction "2_2") (pintype "passive"))
    )
    (net (code "61") (name "Net-(OK3B-COL)") (class "Default")
      (node (ref "LED4") (pin "C") (pinfunction "C_C") (pintype "passive"))
      (node (ref "OK3") (pin "14") (pinfunction "COL_14") (pintype "passive"))
      (node (ref "R10") (pin "2") (pinfunction "2_2") (pintype "passive"))
    )
    (net (code "62") (name "Net-(OK3C-A)") (class "Default")
      (node (ref "OK3") (pin "5") (pinfunction "A_5") (pintype "passive"))
      (node (ref "R5") (pin "2") (pinfunction "2_2") (pintype "passive"))
    )
    (net (code "63") (name "Net-(OK3C-COL)") (class "Default")
      (node (ref "LED5") (pin "C") (pinfunction "C_C") (pintype "passive"))
      (node (ref "OK3") (pin "12") (pinfunction "COL_12") (pintype "passive"))
      (node (ref "R11") (pin "2") (pinfunction "2_2") (pintype "passive"))
    )
    (net (code "64") (name "Net-(OK3D-A)") (class "Default")
      (node (ref "OK3") (pin "7") (pinfunction "A_7") (pintype "passive"))
      (node (ref "R6") (pin "2") (pinfunction "2_2") (pintype "passive"))
    )
    (net (code "65") (name "Net-(OK3D-COL)") (class "Default")
      (node (ref "LED6") (pin "C") (pinfunction "C_C") (pintype "passive"))
      (node (ref "OK3") (pin "10") (pinfunction "COL_10") (pintype "passive"))
      (node (ref "R12") (pin "2") (pinfunction "2_2") (pintype "passive"))
    )
    (net (code "66") (name "Net-(Q1-G)") (class "Default")
      (node (ref "Q1") (pin "1") (pinfunction "G_1") (pintype "passive"))
      (node (ref "R19") (pin "1") (pinfunction "1_1") (pintype "passive"))
      (node (ref "R7") (pin "1") (pinfunction "1_1") (pintype "passive"))
    )
    (net (code "67") (name "Net-(Q2-G)") (class "Default")
      (node (ref "Q2") (pin "1") (pinfunction "G_1") (pintype "passive"))
      (node (ref "R20") (pin "1") (pinfunction "1_1") (pintype "passive"))
      (node (ref "R8") (pin "1") (pinfunction "1_1") (pintype "passive"))
    )
    (net (code "68") (name "Net-(Q3-G)") (class "Default")
      (node (ref "Q3") (pin "1") (pinfunction "G_1") (pintype "passive"))
      (node (ref "R21") (pin "1") (pinfunction "1_1") (pintype "passive"))
      (node (ref "R9") (pin "1") (pinfunction "1_1") (pintype "passive"))
    )
    (net (code "69") (name "Net-(Q4-G)") (class "Default")
      (node (ref "Q4") (pin "1") (pinfunction "G_1") (pintype "passive"))
      (node (ref "R10") (pin "1") (pinfunction "1_1") (pintype "passive"))
      (node (ref "R22") (pin "1") (pinfunction "1_1") (pintype "passive"))
    )
    (net (code "70") (name "Net-(Q5-G)") (class "Default")
      (node (ref "Q5") (pin "1") (pinfunction "G_1") (pintype "passive"))
      (node (ref "R11") (pin "1") (pinfunction "1_1") (pintype "passive"))
      (node (ref "R23") (pin "1") (pinfunction "1_1") (pintype "passive"))
    )
    (net (code "71") (name "Net-(Q6-G)") (class "Default")
      (node (ref "Q6") (pin "1") (pinfunction "G_1") (pintype "passive"))
      (node (ref "R12") (pin "1") (pinfunction "1_1") (pintype "passive"))
      (node (ref "R24") (pin "1") (pinfunction "1_1") (pintype "passive"))
    )
  )
)
